# node_v1.net
KiCad netlist of a schematic drawn in EAGLE
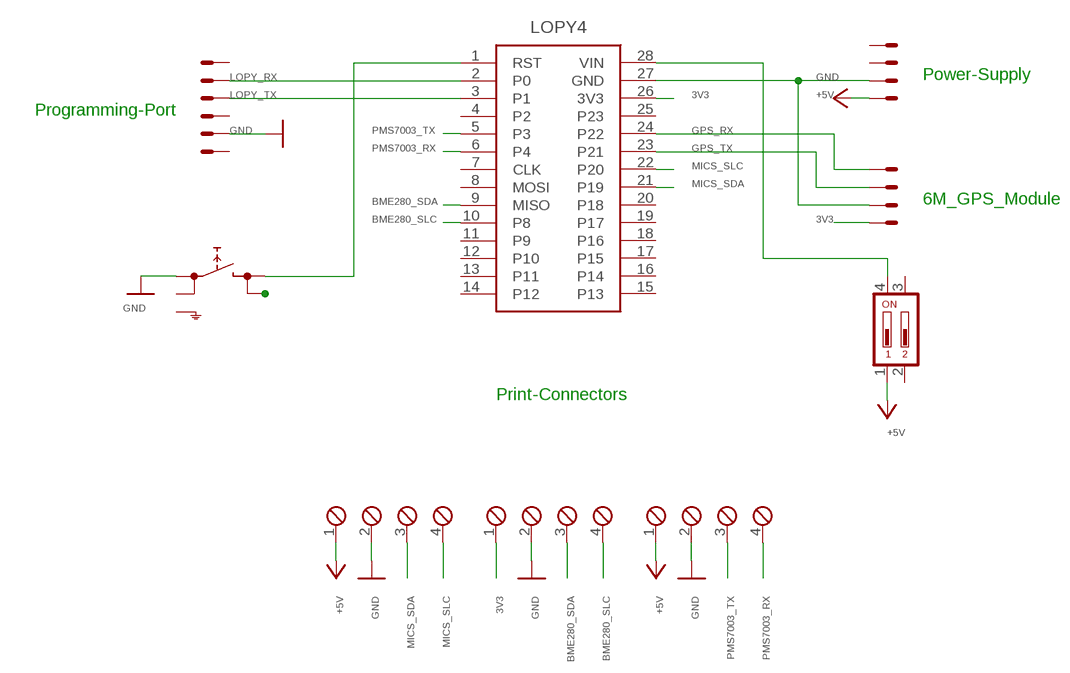
[diagram p0: schematic, sheet 1]

(export (version "E")
  (design (tool "Eeschema 10.0.6"))
  (components
    (comp (ref "5V")
      (value "MPT4")
      (footprint "eagle-import:4POL254")
      (libsource (lib "eagle-import") (part "MPT4"))
    )
    (comp (ref "GND")
      (value "22-23-2041")
      (footprint "eagle-import:22-23-2041")
      (fields (field (name "MF") "MOLEX"))
      (libsource (lib "eagle-import") (part "22-23-2041"))
    )
    (comp (ref "IC1")
      (value "LOPY4")
      (footprint "eagle-import:LOPY4")
      (fields (field (name "MOUSER_PART_NUMBER") "365-LOPY4"))
      (libsource (lib "eagle-import") (part "LOPY4"))
    )
    (comp (ref "S1")
      (value "DA02")
      (footprint "eagle-import:DA-02")
      (libsource (lib "eagle-import") (part "DA02"))
    )
    (comp (ref "S2")
      (value "SKHMPSE010")
      (footprint "eagle-import:SKHMPXE010")
      (libsource (lib "eagle-import") (part "SKHMPE010S"))
    )
    (comp (ref "X1")
      (value "22-23-2061")
      (footprint "eagle-import:22-23-2061")
      (fields (field (name "MF") "MOLEX"))
      (libsource (lib "eagle-import") (part "22-23-2061"))
    )
    (comp (ref "X2")
      (value "MPT4")
      (footprint "eagle-import:4POL254")
      (libsource (lib "eagle-import") (part "MPT4"))
    )
    (comp (ref "X3")
      (value "MPT4")
      (footprint "eagle-import:4POL254")
      (libsource (lib "eagle-import") (part "MPT4"))
    )
    (comp (ref "X4")
      (value "22-23-2041")
      (footprint "eagle-import:22-23-2041")
      (fields (field (name "MF") "MOLEX"))
      (libsource (lib "eagle-import") (part "22-23-2041"))
    )
  )
  (nets
    (net (code "1") (name "+5V") (class "Default")
      (node (ref "5V") (pin "1") (pinfunction "1_1") (pintype "passive"))
      (node (ref "GND") (pin "4") (pinfunction "S_4") (pintype "passive"))
      (node (ref "S1") (pin "1") (pinfunction "1_1") (pintype "passive"))
      (node (ref "X3") (pin "1") (pinfunction "1_1") (pintype "passive"))
    )
    (net (code "2") (name "/3V3") (class "Default")
      (node (ref "IC1") (pin "26") (pinfunction "3V3_26") (pintype "bidirectional"))
      (node (ref "X2") (pin "1") (pinfunction "1_1") (pintype "passive"))
      (node (ref "X4") (pin "4") (pinfunction "S_4") (pintype "passive"))
    )
    (net (code "3") (name "/BME280_SDA") (class "Default")
      (node (ref "IC1") (pin "9") (pinfunction "MISO_9") (pintype "bidirectional"))
      (node (ref "X2") (pin "3") (pinfunction "1_3") (pintype "passive"))
    )
    (net (code "4") (name "/BME280_SLC") (class "Default")
      (node (ref "IC1") (pin "10") (pinfunction "P8_10") (pintype "bidirectional"))
      (node (ref "X2") (pin "4") (pinfunction "1_4") (pintype "passive"))
    )
    (net (code "5") (name "/GPS_RX") (class "Default")
      (node (ref "IC1") (pin "24") (pinfunction "P22_24") (pintype "bidirectional"))
      (node (ref "X4") (pin "1") (pinfunction "S_1") (pintype "passive"))
    )
    (net (code "6") (name "/GPS_TX") (class "Default")
      (node (ref "IC1") (pin "23") (pinfunction "P21_23") (pintype "bidirectional"))
      (node (ref "X4") (pin "2") (pinfunction "S_2") (pintype "passive"))
    )
    (net (code "7") (name "/LOPY_RX") (class "Default")
      (node (ref "IC1") (pin "2") (pinfunction "P0_2") (pintype "bidirectional"))
      (node (ref "X1") (pin "5") (pinfunction "S_5") (pintype "passive"))
    )
    (net (code "8") (name "/LOPY_TX") (class "Default")
      (node (ref "IC1") (pin "3") (pinfunction "P1_3") (pintype "bidirectional"))
      (node (ref "X1") (pin "4") (pinfunction "S_4") (pintype "passive"))
    )
    (net (code "9") (name "/MICS_SDA") (class "Default")
      (node (ref "5V") (pin "3") (pinfunction "1_3") (pintype "passive"))
      (node (ref "IC1") (pin "21") (pinfunction "P19_21") (pintype "bidirectional"))
    )
    (net (code "10") (name "/MICS_SLC") (class "Default")
      (node (ref "5V") (pin "4") (pinfunction "1_4") (pintype "passive"))
      (node (ref "IC1") (pin "22") (pinfunction "P20_22") (pintype "bidirectional"))
    )
    (net (code "11") (name "/PMS7003_RX") (class "Default")
      (node (ref "IC1") (pin "6") (pinfunction "P4_6") (pintype "bidirectional"))
      (node (ref "X3") (pin "4") (pinfunction "1_4") (pintype "passive"))
    )
    (net (code "12") (name "/PMS7003_TX") (class "Default")
      (node (ref "IC1") (pin "5") (pinfunction "P3_5") (pintype "bidirectional"))
      (node (ref "X3") (pin "3") (pinfunction "1_3") (pintype "passive"))
    )
    (net (code "13") (name "GND") (class "Default")
      (node (ref "5V") (pin "2") (pinfunction "1_2") (pintype "passive"))
      (node (ref "GND") (pin "3") (pinfunction "S_3") (pintype "passive"))
      (node (ref "IC1") (pin "27") (pinfunction "GND_27") (pintype "bidirectional"))
      (node (ref "S2") (pin "1") (pinfunction "1.1_1") (pintype "passive"))
      (node (ref "X1") (pin "2") (pinfunction "S_2") (pintype "passive"))
      (node (ref "X2") (pin "2") (pinfunction "1_2") (pintype "passive"))
      (node (ref "X3") (pin "2") (pinfunction "1_2") (pintype "passive"))
      (node (ref "X4") (pin "3") (pinfunction "S_3") (pintype "passive"))
    )
    (net (code "14") (name "Net-(IC1-RST)") (class "Default")
      (node (ref "IC1") (pin "1") (pinfunction "RST_1") (pintype "bidirectional"))
      (node (ref "S2") (pin "3") (pinfunction "2.1_3") (pintype "passive"))
    )
    (net (code "15") (name "Net-(IC1-VIN)") (class "Default")
      (node (ref "IC1") (pin "28") (pinfunction "VIN_28") (pintype "bidirectional"))
      (node (ref "S1") (pin "4") (pinfunction "4_4") (pintype "passive"))
    )
    (net (code "16") (name "unconnected-(GNDA-S-Pad1)") (class "Default")
      (node (ref "GND") (pin "1") (pinfunction "S_1") (pintype "passive"))
    )
    (net (code "17") (name "unconnected-(GNDB-S-Pad2)") (class "Default")
      (node (ref "GND") (pin "2") (pinfunction "S_2") (pintype "passive"))
    )
    (net (code "18") (name "unconnected-(IC1-CLK-Pad7)") (class "Default")
      (node (ref "IC1") (pin "7") (pinfunction "CLK_7") (pintype "bidirectional"))
    )
    (net (code "19") (name "unconnected-(IC1-MOSI-Pad8)") (class "Default")
      (node (ref "IC1") (pin "8") (pinfunction "MOSI_8") (pintype "bidirectional"))
    )
    (net (code "20") (name "unconnected-(IC1-P2-Pad4)") (class "Default")
      (node (ref "IC1") (pin "4") (pinfunction "P2_4") (pintype "bidirectional"))
    )
    (net (code "21") (name "unconnected-(IC1-P9-Pad11)") (class "Default")
      (node (ref "IC1") (pin "11") (pinfunction "P9_11") (pintype "bidirectional"))
    )
    (net (code "22") (name "unconnected-(IC1-P10-Pad12)") (class "Default")
      (node (ref "IC1") (pin "12") (pinfunction "P10_12") (pintype "bidirectional"))
    )
    (net (code "23") (name "unconnected-(IC1-P11-Pad13)") (class "Default")
      (node (ref "IC1") (pin "13") (pinfunction "P11_13") (pintype "bidirectional"))
    )
    (net (code "24") (name "unconnected-(IC1-P12-Pad14)") (class "Default")
      (node (ref "IC1") (pin "14") (pinfunction "P12_14") (pintype "bidirectional"))
    )
    (net (code "25") (name "unconnected-(IC1-P13-Pad15)") (class "Default")
      (node (ref "IC1") (pin "15") (pinfunction "P13_15") (pintype "bidirectional"))
    )
    (net (code "26") (name "unconnected-(IC1-P14-Pad16)") (class "Default")
      (node (ref "IC1") (pin "16") (pinfunction "P14_16") (pintype "bidirectional"))
    )
    (net (code "27") (name "unconnected-(IC1-P15-Pad17)") (class "Default")
      (node (ref "IC1") (pin "17") (pinfunction "P15_17") (pintype "bidirectional"))
    )
    (net (code "28") (name "unconnected-(IC1-P16-Pad18)") (class "Default")
      (node (ref "IC1") (pin "18") (pinfunction "P16_18") (pintype "bidirectional"))
    )
    (net (code "29") (name "unconnected-(IC1-P17-Pad19)") (class "Default")
      (node (ref "IC1") (pin "19") (pinfunction "P17_19") (pintype "bidirectional"))
    )
    (net (code "30") (name "unconnected-(IC1-P18-Pad20)") (class "Default")
      (node (ref "IC1") (pin "20") (pinfunction "P18_20") (pintype "bidirectional"))
    )
    (net (code "31") (name "unconnected-(IC1-P23-Pad25)") (class "Default")
      (node (ref "IC1") (pin "25") (pinfunction "P23_25") (pintype "bidirectional"))
    )
    (net (code "32") (name "unconnected-(S1-Pad2)") (class "Default")
      (node (ref "S1") (pin "2") (pinfunction "2_2") (pintype "passive"))
    )
    (net (code "33") (name "unconnected-(S1-Pad3)") (class "Default")
      (node (ref "S1") (pin "3") (pinfunction "3_3") (pintype "passive"))
    )
    (net (code "34") (name "unconnected-(S2-1.2-Pad2)") (class "Default")
      (node (ref "S2") (pin "2") (pinfunction "1.2_2") (pintype "passive"))
    )
    (net (code "35") (name "unconnected-(S2-2.2-Pad4)") (class "Default")
      (node (ref "S2") (pin "4") (pinfunction "2.2_4") (pintype "passive"))
    )
    (net (code "36") (name "unconnected-(S2-SH-Pad5)") (class "Default")
      (node (ref "S2") (pin "5") (pinfunction "SH_5") (pintype "passive"))
    )
    (net (code "37") (name "unconnected-(X1A-S-Pad1)") (class "Default")
      (node (ref "X1") (pin "1") (pinfunction "S_1") (pintype "passive"))
    )
    (net (code "38") (name "unconnected-(X1C-S-Pad3)") (class "Default")
      (node (ref "X1") (pin "3") (pinfunction "S_3") (pintype "passive"))
    )
    (net (code "39") (name "unconnected-(X1F-S-Pad6)") (class "Default")
      (node (ref "X1") (pin "6") (pinfunction "S_6") (pintype "passive"))
    )
  )
)
